# v1_0.net
KiCad netlist of a schematic drawn in Altium Designer
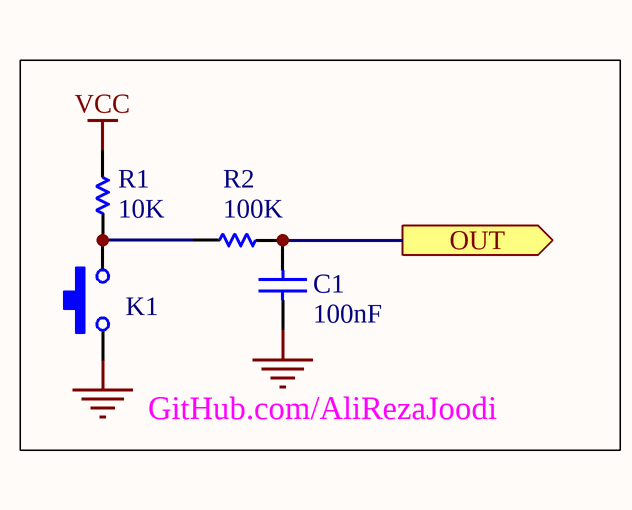
[diagram p0: v1.0.SchDoc]

(export (version "E")
  (design (tool "Eeschema 10.0.6"))
  (components
    (comp (ref "C1")
      (value "100nF")
      (footprint "CAPNTO2.54-3.56x2.03")
      (description "Capacitor")
      (fields (field (name "MANUFACTURER") "Generic Components") (field (name "PUBLISHER") "Altium Limited"))
      (libsource (lib "Miscellaneous Devices") (part "Cap"))
    )
    (comp (ref "K1")
      (value "Switch_SW-PB")
      (footprint "SWPBT_SPST_6X6X4")
      (description "Switch, SW-PB")
      (fields (field (name "MANUFACTURER") "Generic Components") (field (name "PUBLISHER") "Altium Limited"))
      (libsource (lib "General") (part "Switch_SW-PB_2Form"))
    )
    (comp (ref "R1")
      (value "10K")
      (footprint "R_THD_AXIAL0.4(1/4W)")
      (description "Resistor")
      (libsource (lib "General") (part "Resistor"))
    )
    (comp (ref "R2")
      (value "100K")
      (footprint "R_THD_AXIAL0.4(1/4W)")
      (description "Resistor")
      (libsource (lib "General") (part "Resistor"))
    )
  )
  (nets
    (net (code "1") (name "/OUT") (class "Default")
      (node (ref "C1") (pin "1") (pinfunction "1_1") (pintype "passive"))
      (node (ref "R2") (pin "1") (pinfunction "1_1") (pintype "passive"))
    )
    (net (code "2") (name "GND") (class "Default")
      (node (ref "C1") (pin "2") (pinfunction "2_2") (pintype "passive"))
      (node (ref "K1") (pin "1") (pinfunction "1_1") (pintype "passive"))
    )
    (net (code "3") (name "Net-(K1-Pad2)") (class "Default")
      (node (ref "K1") (pin "2") (pinfunction "2_2") (pintype "passive"))
      (node (ref "R1") (pin "1") (pinfunction "1_1") (pintype "passive"))
      (node (ref "R2") (pin "2") (pinfunction "2_2") (pintype "passive"))
    )
    (net (code "4") (name "VCC") (class "Default")
      (node (ref "R1") (pin "2") (pinfunction "2_2") (pintype "passive"))
    )
  )
)
